# tht_3_beta2.net
KiCad netlist of a schematic drawn in EAGLE
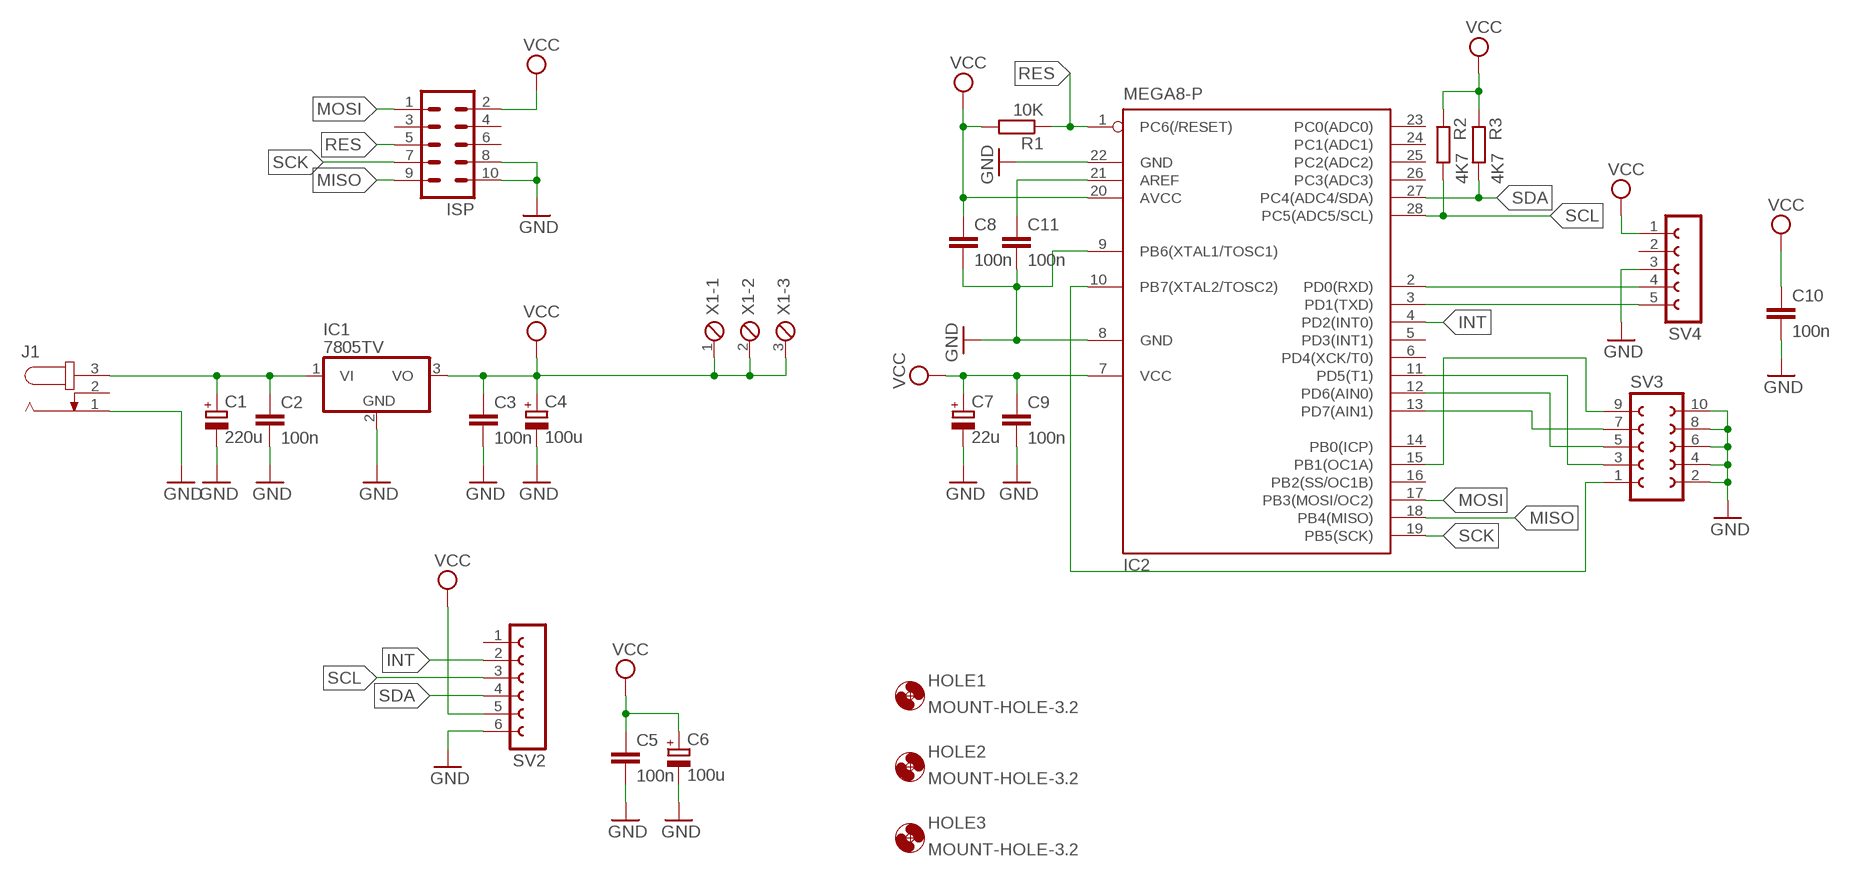
[diagram p0: schematic, sheet 1]

(export (version "E")
  (design (tool "Eeschema 10.0.6"))
  (components
    (comp (ref "C1")
      (value "220u")
      (footprint "eagle-import:E3,5-8")
      (libsource (lib "eagle-import") (part "CPOL-EUE3.5-8"))
    )
    (comp (ref "C2")
      (value "100n")
      (footprint "eagle-import:C025-025X050")
      (libsource (lib "eagle-import") (part "C-EU025-025X050"))
    )
    (comp (ref "C3")
      (value "100n")
      (footprint "eagle-import:C025-025X050")
      (libsource (lib "eagle-import") (part "C-EU025-025X050"))
    )
    (comp (ref "C4")
      (value "100u")
      (footprint "eagle-import:E2,5-5")
      (libsource (lib "eagle-import") (part "CPOL-EUE2.5-5"))
    )
    (comp (ref "C5")
      (value "100n")
      (footprint "eagle-import:C025-025X050")
      (libsource (lib "eagle-import") (part "C-EU025-025X050"))
    )
    (comp (ref "C6")
      (value "100u")
      (footprint "eagle-import:E2,5-5")
      (libsource (lib "eagle-import") (part "CPOL-EUE2.5-5"))
    )
    (comp (ref "C7")
      (value "22u")
      (footprint "eagle-import:E2,5-5")
      (libsource (lib "eagle-import") (part "CPOL-EUE2.5-5"))
    )
    (comp (ref "C8")
      (value "100n")
      (footprint "eagle-import:C025-025X050")
      (libsource (lib "eagle-import") (part "C-EU025-025X050"))
    )
    (comp (ref "C9")
      (value "100n")
      (footprint "eagle-import:C025-030X050")
      (libsource (lib "eagle-import") (part "C-EU025-030X050"))
    )
    (comp (ref "C10")
      (value "100n")
      (footprint "eagle-import:C025-025X050")
      (libsource (lib "eagle-import") (part "C-EU025-025X050"))
    )
    (comp (ref "C11")
      (value "100n")
      (footprint "eagle-import:C025-025X050")
      (libsource (lib "eagle-import") (part "C-EU025-025X050"))
    )
    (comp (ref "HOLE1")
      (value "MOUNT-HOLE-3.2")
      (footprint "eagle-import:3,2")
      (libsource (lib "eagle-import") (part "MOUNT-HOLE-3.2"))
    )
    (comp (ref "HOLE2")
      (value "MOUNT-HOLE-3.2")
      (footprint "eagle-import:3,2")
      (libsource (lib "eagle-import") (part "MOUNT-HOLE-3.2"))
    )
    (comp (ref "HOLE3")
      (value "MOUNT-HOLE-3.2")
      (footprint "eagle-import:3,2")
      (libsource (lib "eagle-import") (part "MOUNT-HOLE-3.2"))
    )
    (comp (ref "IC1")
      (value "7805TV")
      (footprint "eagle-import:TO220V")
      (libsource (lib "eagle-import") (part "78TV05"))
    )
    (comp (ref "IC2")
      (value "MEGA8-P")
      (footprint "eagle-import:DIL28-3")
      (libsource (lib "eagle-import") (part "MEGA8-P"))
    )
    (comp (ref "ISP")
      (value "ML10")
      (footprint "eagle-import:ML10")
      (libsource (lib "eagle-import") (part "ML10"))
    )
    (comp (ref "J1")
      (value "JACK-PLUG1")
      (footprint "eagle-import:SPC4078")
      (libsource (lib "eagle-import") (part "JACK-PLUG1"))
    )
    (comp (ref "R1")
      (value "10K")
      (footprint "eagle-import:0204_7")
      (libsource (lib "eagle-import") (part "R-EU_0204/7"))
    )
    (comp (ref "R2")
      (value "4K7")
      (footprint "eagle-import:0204_7")
      (libsource (lib "eagle-import") (part "R-EU_0204/7"))
    )
    (comp (ref "R3")
      (value "4K7")
      (footprint "eagle-import:0204_7")
      (libsource (lib "eagle-import") (part "R-EU_0204/7"))
    )
    (comp (ref "SV2")
      (value "FE06-1")
      (footprint "eagle-import:FE06")
      (libsource (lib "eagle-import") (part "FE06-1"))
    )
    (comp (ref "SV3")
      (value "FE05-2")
      (footprint "eagle-import:FE05-2")
      (libsource (lib "eagle-import") (part "FE05-2"))
    )
    (comp (ref "SV4")
      (value "FE05-1")
      (footprint "eagle-import:FE05-1")
      (libsource (lib "eagle-import") (part "FE05-1"))
    )
    (comp (ref "X1")
      (value "MPT3")
      (footprint "eagle-import:3POL254")
      (libsource (lib "eagle-import") (part "MPT3"))
    )
  )
  (nets
    (net (code "1") (name "GND") (class "Default")
      (node (ref "C1") (pin "-") (pinfunction "-_-") (pintype "passive"))
      (node (ref "C10") (pin "2") (pinfunction "2_2") (pintype "passive"))
      (node (ref "C11") (pin "2") (pinfunction "2_2") (pintype "passive"))
      (node (ref "C2") (pin "2") (pinfunction "2_2") (pintype "passive"))
      (node (ref "C3") (pin "2") (pinfunction "2_2") (pintype "passive"))
      (node (ref "C4") (pin "-") (pinfunction "-_-") (pintype "passive"))
      (node (ref "C5") (pin "2") (pinfunction "2_2") (pintype "passive"))
      (node (ref "C6") (pin "-") (pinfunction "-_-") (pintype "passive"))
      (node (ref "C7") (pin "-") (pinfunction "-_-") (pintype "passive"))
      (node (ref "C8") (pin "2") (pinfunction "2_2") (pintype "passive"))
      (node (ref "C9") (pin "2") (pinfunction "2_2") (pintype "passive"))
      (node (ref "IC1") (pin "2") (pinfunction "GND_2") (pintype "passive"))
      (node (ref "IC2") (pin "22") (pinfunction "GND_22") (pintype "power_in"))
      (node (ref "IC2") (pin "8") (pinfunction "GND_8") (pintype "power_in"))
      (node (ref "IC2") (pin "9") (pinfunction "PB6(XTAL1/TOSC1)_9") (pintype "bidirectional"))
      (node (ref "ISP") (pin "10") (pinfunction "10_10") (pintype "passive"))
      (node (ref "ISP") (pin "8") (pinfunction "8_8") (pintype "passive"))
      (node (ref "J1") (pin "1") (pinfunction "1_1") (pintype "passive"))
      (node (ref "SV2") (pin "6") (pinfunction "6_6") (pintype "passive"))
      (node (ref "SV3") (pin "10") (pinfunction "10_10") (pintype "passive"))
      (node (ref "SV3") (pin "2") (pinfunction "2_2") (pintype "passive"))
      (node (ref "SV3") (pin "4") (pinfunction "4_4") (pintype "passive"))
      (node (ref "SV3") (pin "6") (pinfunction "6_6") (pintype "passive"))
      (node (ref "SV3") (pin "8") (pinfunction "8_8") (pintype "passive"))
      (node (ref "SV4") (pin "3") (pinfunction "3_3") (pintype "passive"))
    )
    (net (code "2") (name "INT") (class "Default")
      (node (ref "IC2") (pin "4") (pinfunction "PD2(INT0)_4") (pintype "bidirectional"))
      (node (ref "SV2") (pin "2") (pinfunction "2_2") (pintype "passive"))
    )
    (net (code "3") (name "MISO") (class "Default")
      (node (ref "IC2") (pin "18") (pinfunction "PB4(MISO)_18") (pintype "bidirectional"))
      (node (ref "ISP") (pin "9") (pinfunction "9_9") (pintype "passive"))
    )
    (net (code "4") (name "MOSI") (class "Default")
      (node (ref "IC2") (pin "17") (pinfunction "PB3(MOSI/OC2)_17") (pintype "bidirectional"))
      (node (ref "ISP") (pin "1") (pinfunction "1_1") (pintype "passive"))
    )
    (net (code "5") (name "Net-(IC1-VI)") (class "Default")
      (node (ref "C1") (pin "+") (pinfunction "+_+") (pintype "passive"))
      (node (ref "C2") (pin "1") (pinfunction "1_1") (pintype "passive"))
      (node (ref "IC1") (pin "1") (pinfunction "VI_1") (pintype "input"))
      (node (ref "J1") (pin "3") (pinfunction "3_3") (pintype "passive"))
    )
    (net (code "6") (name "Net-(IC2-AREF)") (class "Default")
      (node (ref "C11") (pin "1") (pinfunction "1_1") (pintype "passive"))
      (node (ref "IC2") (pin "21") (pinfunction "AREF_21") (pintype "passive"))
    )
    (net (code "7") (name "Net-(IC2-PB1(OC1A))") (class "Default")
      (node (ref "IC2") (pin "15") (pinfunction "PB1(OC1A)_15") (pintype "bidirectional"))
      (node (ref "SV3") (pin "9") (pinfunction "9_9") (pintype "passive"))
    )
    (net (code "8") (name "Net-(IC2-PB7(XTAL2{slash}TOSC2))") (class "Default")
      (node (ref "IC2") (pin "10") (pinfunction "PB7(XTAL2/TOSC2)_10") (pintype "bidirectional"))
      (node (ref "SV3") (pin "1") (pinfunction "1_1") (pintype "passive"))
    )
    (net (code "9") (name "Net-(IC2-PD0(RXD))") (class "Default")
      (node (ref "IC2") (pin "2") (pinfunction "PD0(RXD)_2") (pintype "bidirectional"))
      (node (ref "SV4") (pin "4") (pinfunction "4_4") (pintype "passive"))
    )
    (net (code "10") (name "Net-(IC2-PD1(TXD))") (class "Default")
      (node (ref "IC2") (pin "3") (pinfunction "PD1(TXD)_3") (pintype "bidirectional"))
      (node (ref "SV4") (pin "5") (pinfunction "5_5") (pintype "passive"))
    )
    (net (code "11") (name "Net-(IC2-PD5(T1))") (class "Default")
      (node (ref "IC2") (pin "11") (pinfunction "PD5(T1)_11") (pintype "bidirectional"))
      (node (ref "SV3") (pin "3") (pinfunction "3_3") (pintype "passive"))
    )
    (net (code "12") (name "Net-(IC2-PD6(AIN0))") (class "Default")
      (node (ref "IC2") (pin "12") (pinfunction "PD6(AIN0)_12") (pintype "bidirectional"))
      (node (ref "SV3") (pin "5") (pinfunction "5_5") (pintype "passive"))
    )
    (net (code "13") (name "Net-(IC2-PD7(AIN1))") (class "Default")
      (node (ref "IC2") (pin "13") (pinfunction "PD7(AIN1)_13") (pintype "bidirectional"))
      (node (ref "SV3") (pin "7") (pinfunction "7_7") (pintype "passive"))
    )
    (net (code "14") (name "RES") (class "Default")
      (node (ref "IC2") (pin "1") (pinfunction "PC6(/RESET)_1") (pintype "bidirectional"))
      (node (ref "ISP") (pin "5") (pinfunction "5_5") (pintype "passive"))
      (node (ref "R1") (pin "1") (pinfunction "1_1") (pintype "passive"))
    )
    (net (code "15") (name "SCK") (class "Default")
      (node (ref "IC2") (pin "19") (pinfunction "PB5(SCK)_19") (pintype "bidirectional"))
      (node (ref "ISP") (pin "7") (pinfunction "7_7") (pintype "passive"))
    )
    (net (code "16") (name "SCL") (class "Default")
      (node (ref "IC2") (pin "28") (pinfunction "PC5(ADC5/SCL)_28") (pintype "bidirectional"))
      (node (ref "R2") (pin "2") (pinfunction "2_2") (pintype "passive"))
      (node (ref "SV2") (pin "3") (pinfunction "3_3") (pintype "passive"))
    )
    (net (code "17") (name "SDA") (class "Default")
      (node (ref "IC2") (pin "27") (pinfunction "PC4(ADC4/SDA)_27") (pintype "bidirectional"))
      (node (ref "R3") (pin "2") (pinfunction "2_2") (pintype "passive"))
      (node (ref "SV2") (pin "4") (pinfunction "4_4") (pintype "passive"))
    )
    (net (code "18") (name "VCC") (class "Default")
      (node (ref "C10") (pin "1") (pinfunction "1_1") (pintype "passive"))
      (node (ref "C3") (pin "1") (pinfunction "1_1") (pintype "passive"))
      (node (ref "C4") (pin "+") (pinfunction "+_+") (pintype "passive"))
      (node (ref "C5") (pin "1") (pinfunction "1_1") (pintype "passive"))
      (node (ref "C6") (pin "+") (pinfunction "+_+") (pintype "passive"))
      (node (ref "C7") (pin "+") (pinfunction "+_+") (pintype "passive"))
      (node (ref "C8") (pin "1") (pinfunction "1_1") (pintype "passive"))
      (node (ref "C9") (pin "1") (pinfunction "1_1") (pintype "passive"))
      (node (ref "IC1") (pin "3") (pinfunction "VO_3") (pintype "passive"))
      (node (ref "IC2") (pin "20") (pinfunction "AVCC_20") (pintype "power_in"))
      (node (ref "IC2") (pin "7") (pinfunction "VCC_7") (pintype "power_in"))
      (node (ref "ISP") (pin "2") (pinfunction "2_2") (pintype "passive"))
      (node (ref "R1") (pin "2") (pinfunction "2_2") (pintype "passive"))
      (node (ref "R2") (pin "1") (pinfunction "1_1") (pintype "passive"))
      (node (ref "R3") (pin "1") (pinfunction "1_1") (pintype "passive"))
      (node (ref "SV2") (pin "5") (pinfunction "5_5") (pintype "passive"))
      (node (ref "SV4") (pin "1") (pinfunction "1_1") (pintype "passive"))
      (node (ref "X1") (pin "1") (pinfunction "1_1") (pintype "passive"))
      (node (ref "X1") (pin "2") (pinfunction "1_2") (pintype "passive"))
      (node (ref "X1") (pin "3") (pinfunction "1_3") (pintype "passive"))
    )
    (net (code "19") (name "unconnected-(IC2-PB0(ICP)-Pad14)") (class "Default")
      (node (ref "IC2") (pin "14") (pinfunction "PB0(ICP)_14") (pintype "bidirectional"))
    )
    (net (code "20") (name "unconnected-(IC2-PB2(SS{slash}OC1B)-Pad16)") (class "Default")
      (node (ref "IC2") (pin "16") (pinfunction "PB2(SS/OC1B)_16") (pintype "bidirectional"))
    )
    (net (code "21") (name "unconnected-(IC2-PC0(ADC0)-Pad23)") (class "Default")
      (node (ref "IC2") (pin "23") (pinfunction "PC0(ADC0)_23") (pintype "bidirectional"))
    )
    (net (code "22") (name "unconnected-(IC2-PC1(ADC1)-Pad24)") (class "Default")
      (node (ref "IC2") (pin "24") (pinfunction "PC1(ADC1)_24") (pintype "bidirectional"))
    )
    (net (code "23") (name "unconnected-(IC2-PC2(ADC2)-Pad25)") (class "Default")
      (node (ref "IC2") (pin "25") (pinfunction "PC2(ADC2)_25") (pintype "bidirectional"))
    )
    (net (code "24") (name "unconnected-(IC2-PC3(ADC3)-Pad26)") (class "Default")
      (node (ref "IC2") (pin "26") (pinfunction "PC3(ADC3)_26") (pintype "bidirectional"))
    )
    (net (code "25") (name "unconnected-(IC2-PD3(INT1)-Pad5)") (class "Default")
      (node (ref "IC2") (pin "5") (pinfunction "PD3(INT1)_5") (pintype "bidirectional"))
    )
    (net (code "26") (name "unconnected-(IC2-PD4(XCK{slash}T0)-Pad6)") (class "Default")
      (node (ref "IC2") (pin "6") (pinfunction "PD4(XCK/T0)_6") (pintype "bidirectional"))
    )
    (net (code "27") (name "unconnected-(ISP-Pad3)") (class "Default")
      (node (ref "ISP") (pin "3") (pinfunction "3_3") (pintype "passive"))
    )
    (net (code "28") (name "unconnected-(ISP-Pad4)") (class "Default")
      (node (ref "ISP") (pin "4") (pinfunction "4_4") (pintype "passive"))
    )
    (net (code "29") (name "unconnected-(ISP-Pad6)") (class "Default")
      (node (ref "ISP") (pin "6") (pinfunction "6_6") (pintype "passive"))
    )
    (net (code "30") (name "unconnected-(J1-Pad2)") (class "Default")
      (node (ref "J1") (pin "2") (pinfunction "2_2") (pintype "passive"))
    )
    (net (code "31") (name "unconnected-(SV2-Pad1)") (class "Default")
      (node (ref "SV2") (pin "1") (pinfunction "1_1") (pintype "passive"))
    )
    (net (code "32") (name "unconnected-(SV4-Pad2)") (class "Default")
      (node (ref "SV4") (pin "2") (pinfunction "2_2") (pintype "passive"))
    )
  )
)
